# mono.net
KiCad netlist of a schematic drawn in EAGLE
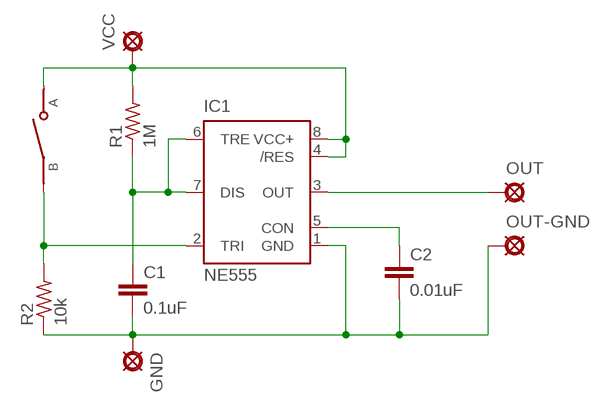
[diagram p0: schematic, sheet 1]

(export (version "E")
  (design (tool "Eeschema 10.0.6"))
  (components
    (comp (ref "C1")
      (value "0.1uF")
      (footprint "eagle-import:050X030_025")
      (libsource (lib "eagle-import") (part "050X030_0251"))
    )
    (comp (ref "C2")
      (value "0.01uF")
      (footprint "eagle-import:050X030_025")
      (libsource (lib "eagle-import") (part "050X030_0251"))
    )
    (comp (ref "GND")
      (value "PAD8")
      (footprint "eagle-import:OCTOGON")
      (libsource (lib "eagle-import") (part "PAD8"))
    )
    (comp (ref "IC1")
      (value "NE555")
      (footprint "eagle-import:DIL-08")
      (fields (field (name "MF") "Arrow Electronics") (field (name "MPN") "NE555N"))
      (libsource (lib "eagle-import") (part "NE555"))
    )
    (comp (ref "OUT")
      (value "PAD")
      (footprint "eagle-import:SQUARE")
      (libsource (lib "eagle-import") (part "PAD"))
    )
    (comp (ref "OUT-GND")
      (value "PAD")
      (footprint "eagle-import:SQUARE")
      (libsource (lib "eagle-import") (part "PAD"))
    )
    (comp (ref "R1")
      (value "1M")
      (footprint "eagle-import:R0207_4")
      (libsource (lib "eagle-import") (part "6MM.4"))
    )
    (comp (ref "R2")
      (value "10k")
      (footprint "eagle-import:R0207_4")
      (libsource (lib "eagle-import") (part "6MM.4"))
    )
    (comp (ref "SW1")
      (value "SPST_SWITCH")
      (footprint "eagle-import:SPST_TOGGLE_SWITCH")
      (libsource (lib "eagle-import") (part "SPST_SWITCH"))
    )
    (comp (ref "VCC")
      (value "PAD")
      (footprint "eagle-import:SQUARE")
      (libsource (lib "eagle-import") (part "PAD"))
    )
  )
  (nets
    (net (code "1") (name "Net-(GND-PAD)") (class "Default")
      (node (ref "C1") (pin "2") (pinfunction "2_2") (pintype "passive"))
      (node (ref "C2") (pin "2") (pinfunction "2_2") (pintype "passive"))
      (node (ref "GND") (pin "1") (pinfunction "PAD_1") (pintype "passive"))
      (node (ref "IC1") (pin "1") (pinfunction "GND_1") (pintype "power_in"))
      (node (ref "OUT-GND") (pin "1") (pinfunction "PAD_1") (pintype "passive"))
      (node (ref "R2") (pin "1") (pinfunction "1_1") (pintype "passive"))
    )
    (net (code "2") (name "Net-(IC1-CON)") (class "Default")
      (node (ref "C2") (pin "1") (pinfunction "1_1") (pintype "passive"))
      (node (ref "IC1") (pin "5") (pinfunction "CON_5") (pintype "input"))
    )
    (net (code "3") (name "Net-(IC1-DIS)") (class "Default")
      (node (ref "C1") (pin "1") (pinfunction "1_1") (pintype "passive"))
      (node (ref "IC1") (pin "6") (pinfunction "TRE_6") (pintype "input"))
      (node (ref "IC1") (pin "7") (pinfunction "DIS_7") (pintype "input"))
      (node (ref "R1") (pin "1") (pinfunction "1_1") (pintype "passive"))
    )
    (net (code "4") (name "Net-(IC1-OUT)") (class "Default")
      (node (ref "IC1") (pin "3") (pinfunction "OUT_3") (pintype "output"))
      (node (ref "OUT") (pin "1") (pinfunction "PAD_1") (pintype "passive"))
    )
    (net (code "5") (name "Net-(IC1-TRI)") (class "Default")
      (node (ref "IC1") (pin "2") (pinfunction "TRI_2") (pintype "input"))
      (node (ref "R2") (pin "2") (pinfunction "2_2") (pintype "passive"))
      (node (ref "SW1") (pin "B") (pinfunction "B_B") (pintype "passive"))
    )
    (net (code "6") (name "Net-(IC1-VCC+)") (class "Default")
      (node (ref "IC1") (pin "4") (pinfunction "/RES_4") (pintype "input"))
      (node (ref "IC1") (pin "8") (pinfunction "VCC+_8") (pintype "power_in"))
      (node (ref "R1") (pin "2") (pinfunction "2_2") (pintype "passive"))
      (node (ref "SW1") (pin "A") (pinfunction "A_A") (pintype "passive"))
      (node (ref "VCC") (pin "1") (pinfunction "PAD_1") (pintype "passive"))
    )
  )
)
